# Power.net
KiCad netlist of a schematic drawn in Altium Designer
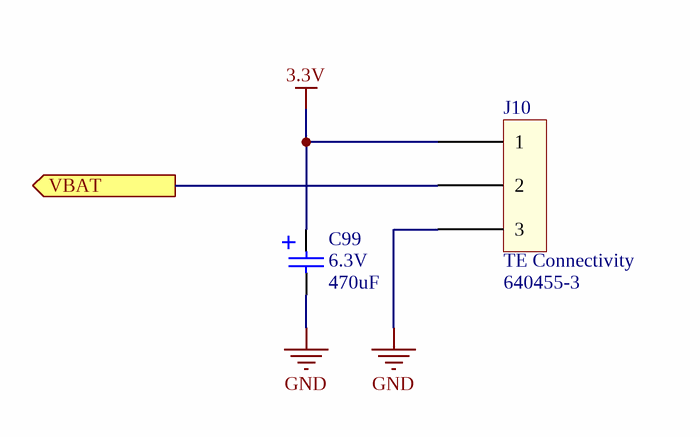
[diagram p0: Power.SchDoc]

(export (version "E")
  (design (tool "Eeschema 10.0.6"))
  (components
    (comp (ref "C99")
      (value "470uF")
      (footprint "CAP_ALUM_SIZE_F")
      (description "CAP ALUM 470UF 20% 6.3V SMD")
      (fields
        (field (name "MANUFACTURER") "Panasonic")
        (field (name "VOLTAGE") "6.3V")
        (field (name "Comment") "EEE-FK0J471P")
      )
      (libsource (lib "Panasonic") (part "EEE-FK0J471P"))
    )
    (comp (ref "J10")
      (value "640455-3")
      (footprint "TE-640455-3")
      (description "CONN HEADER RTANG 3POS .100 TIN")
      (fields (field (name "MANUFACTURER") "TE Connectivity") (field (name "PARTNUMBER") "640455-3"))
      (libsource (lib "TeConnectivity") (part "640455-3"))
    )
  )
  (nets
    (net (code "1") (name "/VBAT") (class "Default")
      (node (ref "J10") (pin "2") (pinfunction "2_2") (pintype "passive"))
    )
    (net (code "2") (name "3.3V") (class "Default")
      (node (ref "C99") (pin "1") (pinfunction "1_1") (pintype "passive"))
      (node (ref "J10") (pin "1") (pinfunction "1_1") (pintype "passive"))
    )
    (net (code "3") (name "GND") (class "Default")
      (node (ref "C99") (pin "2") (pinfunction "2_2") (pintype "passive"))
      (node (ref "J10") (pin "3") (pinfunction "3_3") (pintype "passive"))
    )
  )
)
